# Pcon.net
KiCad netlist of a schematic drawn in EAGLE
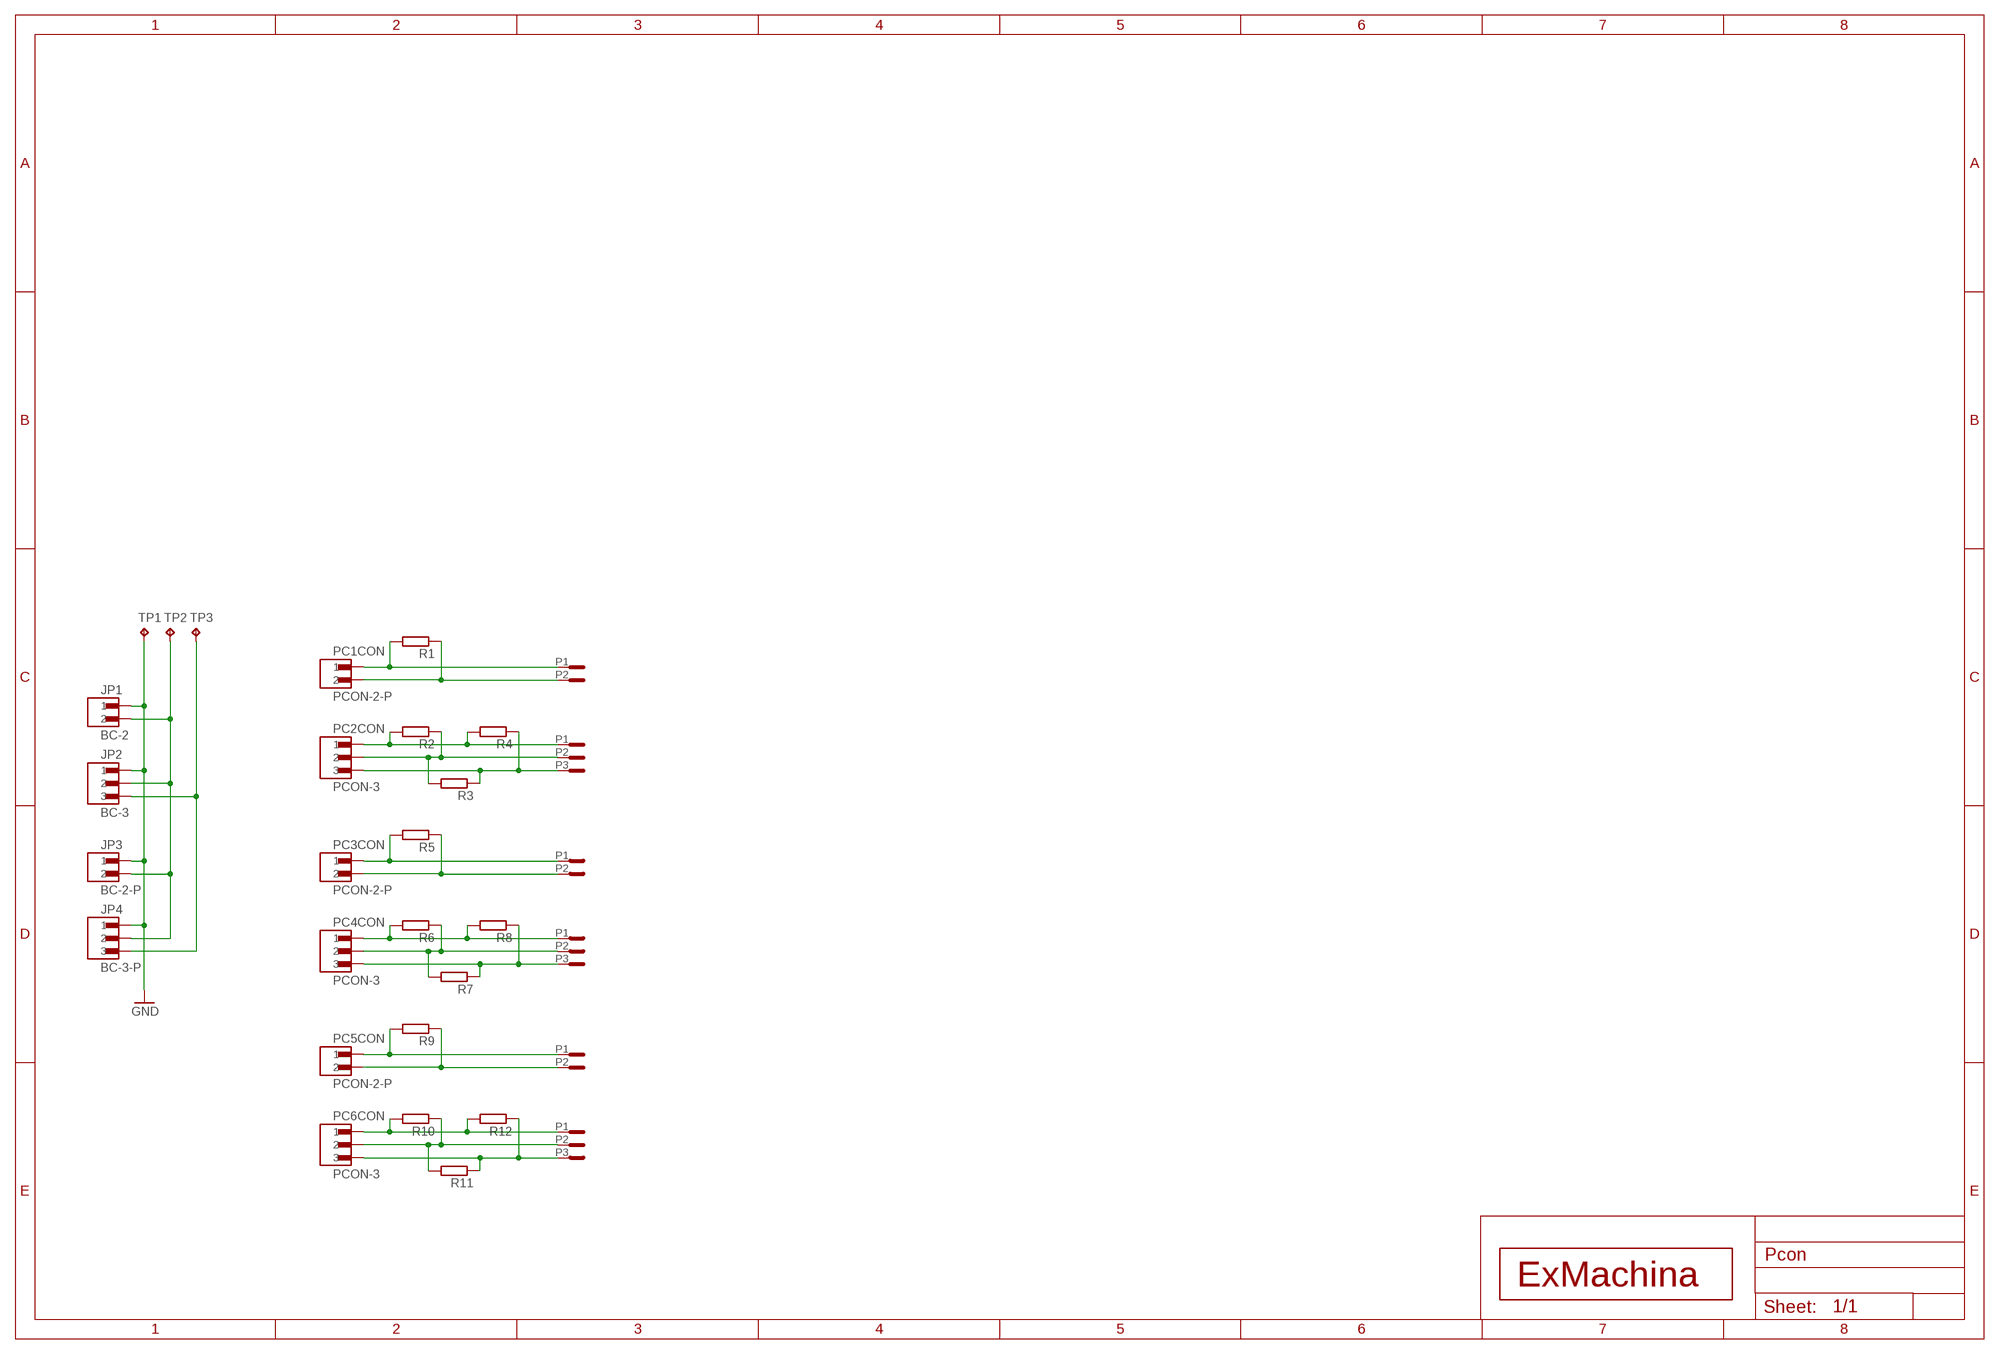
[diagram p0: schematic, sheet 1]

(export (version "E")
  (design (tool "Eeschema 10.0.6"))
  (components
    (comp (ref "JP1")
      (value "BC-2")
      (footprint "eagle-import:BC-2")
      (libsource (lib "eagle-import") (part "BC-2?"))
    )
    (comp (ref "JP2")
      (value "BC-3")
      (footprint "eagle-import:BC-3")
      (libsource (lib "eagle-import") (part "BC-3?"))
    )
    (comp (ref "JP3")
      (value "BC-2-P")
      (footprint "eagle-import:BC-2-P")
      (libsource (lib "eagle-import") (part "BC-2?-P"))
    )
    (comp (ref "JP4")
      (value "BC-3-P")
      (footprint "eagle-import:BC-3-P")
      (libsource (lib "eagle-import") (part "BC-3?-P"))
    )
    (comp (ref "PC1")
      (value "PCON-2-P")
      (footprint "eagle-import:PCON-2")
      (libsource (lib "eagle-import") (part "PCON-2?-P"))
    )
    (comp (ref "PC2")
      (value "PCON-3")
      (footprint "eagle-import:PCON-3")
      (libsource (lib "eagle-import") (part "PCON-3?"))
    )
    (comp (ref "PC3")
      (value "PCON-2-P")
      (footprint "eagle-import:PCON-2")
      (libsource (lib "eagle-import") (part "PCON-2?-P"))
    )
    (comp (ref "PC4")
      (value "PCON-3")
      (footprint "eagle-import:PCON-3")
      (libsource (lib "eagle-import") (part "PCON-3?"))
    )
    (comp (ref "PC5")
      (value "PCON-2-P")
      (footprint "eagle-import:PCON-2")
      (libsource (lib "eagle-import") (part "PCON-2?-P"))
    )
    (comp (ref "PC6")
      (value "PCON-3")
      (footprint "eagle-import:PCON-3")
      (libsource (lib "eagle-import") (part "PCON-3?"))
    )
    (comp (ref "R1")
      (value "R-EU_R0603")
      (footprint "eagle-import:R0603")
      (libsource (lib "eagle-import") (part "R-EU_R0603"))
    )
    (comp (ref "R2")
      (value "R-EU_R0603")
      (footprint "eagle-import:R0603")
      (libsource (lib "eagle-import") (part "R-EU_R0603"))
    )
    (comp (ref "R3")
      (value "R-EU_R0603")
      (footprint "eagle-import:R0603")
      (libsource (lib "eagle-import") (part "R-EU_R0603"))
    )
    (comp (ref "R4")
      (value "R-EU_R0603")
      (footprint "eagle-import:R0603")
      (libsource (lib "eagle-import") (part "R-EU_R0603"))
    )
    (comp (ref "R5")
      (value "R-EU_R0603")
      (footprint "eagle-import:R0603")
      (libsource (lib "eagle-import") (part "R-EU_R0603"))
    )
    (comp (ref "R6")
      (value "R-EU_R0603")
      (footprint "eagle-import:R0603")
      (libsource (lib "eagle-import") (part "R-EU_R0603"))
    )
    (comp (ref "R7")
      (value "R-EU_R0603")
      (footprint "eagle-import:R0603")
      (libsource (lib "eagle-import") (part "R-EU_R0603"))
    )
    (comp (ref "R8")
      (value "R-EU_R0603")
      (footprint "eagle-import:R0603")
      (libsource (lib "eagle-import") (part "R-EU_R0603"))
    )
    (comp (ref "R9")
      (value "R-EU_R0603")
      (footprint "eagle-import:R0603")
      (libsource (lib "eagle-import") (part "R-EU_R0603"))
    )
    (comp (ref "R10")
      (value "R-EU_R0603")
      (footprint "eagle-import:R0603")
      (libsource (lib "eagle-import") (part "R-EU_R0603"))
    )
    (comp (ref "R11")
      (value "R-EU_R0603")
      (footprint "eagle-import:R0603")
      (libsource (lib "eagle-import") (part "R-EU_R0603"))
    )
    (comp (ref "R12")
      (value "R-EU_R0603")
      (footprint "eagle-import:R0603")
      (libsource (lib "eagle-import") (part "R-EU_R0603"))
    )
    (comp (ref "TP1")
      (value "TPB1,27")
      (footprint "eagle-import:B1,27")
      (libsource (lib "eagle-import") (part "TPB1,27"))
    )
    (comp (ref "TP2")
      (value "TPB1,27")
      (footprint "eagle-import:B1,27")
      (libsource (lib "eagle-import") (part "TPB1,27"))
    )
    (comp (ref "TP3")
      (value "TPB1,27")
      (footprint "eagle-import:B1,27")
      (libsource (lib "eagle-import") (part "TPB1,27"))
    )
    (comp (ref "U$1")
      (value "EXMACHINA-LOGO")
      (footprint "eagle-import:EXM-LOGO")
      (libsource (lib "eagle-import") (part "EXMACHINA-LOGO"))
    )
  )
  (nets
    (net (code "1") (name "GND") (class "Default")
      (node (ref "JP1") (pin "1") (pinfunction "1_1") (pintype "bidirectional"))
      (node (ref "JP2") (pin "1") (pinfunction "1_1") (pintype "bidirectional"))
      (node (ref "JP3") (pin "1") (pinfunction "1_1") (pintype "bidirectional"))
      (node (ref "JP4") (pin "1") (pinfunction "1_1") (pintype "bidirectional"))
      (node (ref "TP1") (pin "TP") (pinfunction "TP_TP") (pintype "input"))
    )
    (net (code "2") (name "Net-(JP1-Pad2)") (class "Default")
      (node (ref "JP1") (pin "2") (pinfunction "2_2") (pintype "bidirectional"))
      (node (ref "JP2") (pin "2") (pinfunction "2_2") (pintype "bidirectional"))
      (node (ref "JP3") (pin "2") (pinfunction "2_2") (pintype "bidirectional"))
      (node (ref "JP4") (pin "2") (pinfunction "2_2") (pintype "bidirectional"))
      (node (ref "TP2") (pin "TP") (pinfunction "TP_TP") (pintype "input"))
    )
    (net (code "3") (name "Net-(JP2-Pad3)") (class "Default")
      (node (ref "JP2") (pin "3") (pinfunction "3_3") (pintype "bidirectional"))
      (node (ref "JP4") (pin "3") (pinfunction "3_3") (pintype "bidirectional"))
      (node (ref "TP3") (pin "TP") (pinfunction "TP_TP") (pintype "input"))
    )
    (net (code "4") (name "Net-(PC1B-P)") (class "Default")
      (node (ref "PC1") (pin "1") (pinfunction "1_1") (pintype "bidirectional"))
      (node (ref "PC1") (pin "P1") (pinfunction "P_P1") (pintype "bidirectional"))
      (node (ref "R1") (pin "2") (pinfunction "2_2") (pintype "passive"))
    )
    (net (code "5") (name "Net-(PC1C-P)") (class "Default")
      (node (ref "PC1") (pin "2") (pinfunction "2_2") (pintype "bidirectional"))
      (node (ref "PC1") (pin "P2") (pinfunction "P_P2") (pintype "bidirectional"))
      (node (ref "R1") (pin "1") (pinfunction "1_1") (pintype "passive"))
    )
    (net (code "6") (name "Net-(PC2B-P)") (class "Default")
      (node (ref "PC2") (pin "1") (pinfunction "1_1") (pintype "bidirectional"))
      (node (ref "PC2") (pin "P1") (pinfunction "P_P1") (pintype "bidirectional"))
      (node (ref "R2") (pin "2") (pinfunction "2_2") (pintype "passive"))
      (node (ref "R4") (pin "2") (pinfunction "2_2") (pintype "passive"))
    )
    (net (code "7") (name "Net-(PC2C-P)") (class "Default")
      (node (ref "PC2") (pin "2") (pinfunction "2_2") (pintype "bidirectional"))
      (node (ref "PC2") (pin "P2") (pinfunction "P_P2") (pintype "bidirectional"))
      (node (ref "R2") (pin "1") (pinfunction "1_1") (pintype "passive"))
      (node (ref "R3") (pin "2") (pinfunction "2_2") (pintype "passive"))
    )
    (net (code "8") (name "Net-(PC2D-P)") (class "Default")
      (node (ref "PC2") (pin "3") (pinfunction "3_3") (pintype "bidirectional"))
      (node (ref "PC2") (pin "P3") (pinfunction "P_P3") (pintype "bidirectional"))
      (node (ref "R3") (pin "1") (pinfunction "1_1") (pintype "passive"))
      (node (ref "R4") (pin "1") (pinfunction "1_1") (pintype "passive"))
    )
    (net (code "9") (name "Net-(PC3B-P)") (class "Default")
      (node (ref "PC3") (pin "1") (pinfunction "1_1") (pintype "bidirectional"))
      (node (ref "PC3") (pin "P1") (pinfunction "P_P1") (pintype "bidirectional"))
      (node (ref "R5") (pin "2") (pinfunction "2_2") (pintype "passive"))
    )
    (net (code "10") (name "Net-(PC3C-P)") (class "Default")
      (node (ref "PC3") (pin "2") (pinfunction "2_2") (pintype "bidirectional"))
      (node (ref "PC3") (pin "P2") (pinfunction "P_P2") (pintype "bidirectional"))
      (node (ref "R5") (pin "1") (pinfunction "1_1") (pintype "passive"))
    )
    (net (code "11") (name "Net-(PC4B-P)") (class "Default")
      (node (ref "PC4") (pin "1") (pinfunction "1_1") (pintype "bidirectional"))
      (node (ref "PC4") (pin "P1") (pinfunction "P_P1") (pintype "bidirectional"))
      (node (ref "R6") (pin "2") (pinfunction "2_2") (pintype "passive"))
      (node (ref "R8") (pin "2") (pinfunction "2_2") (pintype "passive"))
    )
    (net (code "12") (name "Net-(PC4C-P)") (class "Default")
      (node (ref "PC4") (pin "2") (pinfunction "2_2") (pintype "bidirectional"))
      (node (ref "PC4") (pin "P2") (pinfunction "P_P2") (pintype "bidirectional"))
      (node (ref "R6") (pin "1") (pinfunction "1_1") (pintype "passive"))
      (node (ref "R7") (pin "2") (pinfunction "2_2") (pintype "passive"))
    )
    (net (code "13") (name "Net-(PC4D-P)") (class "Default")
      (node (ref "PC4") (pin "3") (pinfunction "3_3") (pintype "bidirectional"))
      (node (ref "PC4") (pin "P3") (pinfunction "P_P3") (pintype "bidirectional"))
      (node (ref "R7") (pin "1") (pinfunction "1_1") (pintype "passive"))
      (node (ref "R8") (pin "1") (pinfunction "1_1") (pintype "passive"))
    )
    (net (code "14") (name "Net-(PC5B-P)") (class "Default")
      (node (ref "PC5") (pin "1") (pinfunction "1_1") (pintype "bidirectional"))
      (node (ref "PC5") (pin "P1") (pinfunction "P_P1") (pintype "bidirectional"))
      (node (ref "R9") (pin "2") (pinfunction "2_2") (pintype "passive"))
    )
    (net (code "15") (name "Net-(PC5C-P)") (class "Default")
      (node (ref "PC5") (pin "2") (pinfunction "2_2") (pintype "bidirectional"))
      (node (ref "PC5") (pin "P2") (pinfunction "P_P2") (pintype "bidirectional"))
      (node (ref "R9") (pin "1") (pinfunction "1_1") (pintype "passive"))
    )
    (net (code "16") (name "Net-(PC6B-P)") (class "Default")
      (node (ref "PC6") (pin "1") (pinfunction "1_1") (pintype "bidirectional"))
      (node (ref "PC6") (pin "P1") (pinfunction "P_P1") (pintype "bidirectional"))
      (node (ref "R10") (pin "2") (pinfunction "2_2") (pintype "passive"))
      (node (ref "R12") (pin "2") (pinfunction "2_2") (pintype "passive"))
    )
    (net (code "17") (name "Net-(PC6C-P)") (class "Default")
      (node (ref "PC6") (pin "2") (pinfunction "2_2") (pintype "bidirectional"))
      (node (ref "PC6") (pin "P2") (pinfunction "P_P2") (pintype "bidirectional"))
      (node (ref "R10") (pin "1") (pinfunction "1_1") (pintype "passive"))
      (node (ref "R11") (pin "2") (pinfunction "2_2") (pintype "passive"))
    )
    (net (code "18") (name "Net-(PC6D-P)") (class "Default")
      (node (ref "PC6") (pin "3") (pinfunction "3_3") (pintype "bidirectional"))
      (node (ref "PC6") (pin "P3") (pinfunction "P_P3") (pintype "bidirectional"))
      (node (ref "R11") (pin "1") (pinfunction "1_1") (pintype "passive"))
      (node (ref "R12") (pin "1") (pinfunction "1_1") (pintype "passive"))
    )
  )
)
